# ESP-03_Breakout.net
KiCad netlist of a schematic drawn in EAGLE
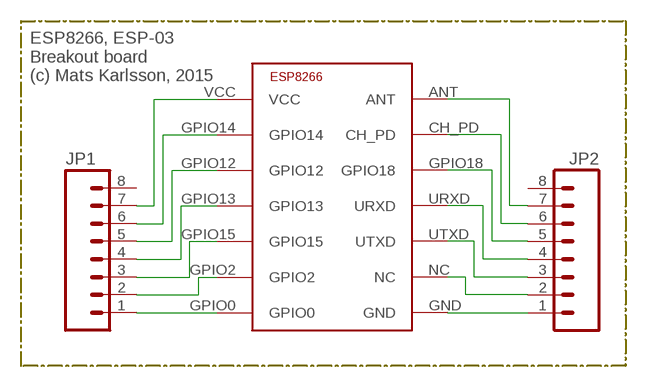
[diagram p0: schematic, sheet 1]

(export (version "E")
  (design (tool "Eeschema 10.0.6"))
  (components
    (comp (ref "JP1")
      (value "M08SMD-STRAIGHT-FEMALE")
      (footprint "eagle-import:1X08_SMD")
      (libsource (lib "eagle-import") (part "M08SMD-STRAIGHT-FEMALE"))
    )
    (comp (ref "JP2")
      (value "M08SMD-STRAIGHT-FEMALE")
      (footprint "eagle-import:1X08_SMD")
      (libsource (lib "eagle-import") (part "M08SMD-STRAIGHT-FEMALE"))
    )
    (comp (ref "U$1")
      (value "ESP8266-03")
      (footprint "eagle-import:ESP-03")
      (libsource (lib "eagle-import") (part "ESP8266-03"))
    )
  )
  (nets
    (net (code "1") (name "Net-(JP1-Pad1)") (class "Default")
      (node (ref "JP1") (pin "1") (pinfunction "1_1") (pintype "passive"))
      (node (ref "U$1") (pin "GPIO0") (pinfunction "GPIO0_GPIO0") (pintype "bidirectional"))
    )
    (net (code "2") (name "Net-(JP1-Pad2)") (class "Default")
      (node (ref "JP1") (pin "2") (pinfunction "2_2") (pintype "passive"))
      (node (ref "U$1") (pin "GPIO2") (pinfunction "GPIO2_GPIO2") (pintype "bidirectional"))
    )
    (net (code "3") (name "Net-(JP1-Pad3)") (class "Default")
      (node (ref "JP1") (pin "3") (pinfunction "3_3") (pintype "passive"))
      (node (ref "U$1") (pin "GPIO15") (pinfunction "GPIO15_GPIO15") (pintype "bidirectional"))
    )
    (net (code "4") (name "Net-(JP1-Pad4)") (class "Default")
      (node (ref "JP1") (pin "4") (pinfunction "4_4") (pintype "passive"))
      (node (ref "U$1") (pin "GPIO13") (pinfunction "GPIO13_GPIO13") (pintype "bidirectional"))
    )
    (net (code "5") (name "Net-(JP1-Pad5)") (class "Default")
      (node (ref "JP1") (pin "5") (pinfunction "5_5") (pintype "passive"))
      (node (ref "U$1") (pin "GPIO12") (pinfunction "GPIO12_GPIO12") (pintype "bidirectional"))
    )
    (net (code "6") (name "Net-(JP1-Pad6)") (class "Default")
      (node (ref "JP1") (pin "6") (pinfunction "6_6") (pintype "passive"))
      (node (ref "U$1") (pin "GPIO14") (pinfunction "GPIO14_GPIO14") (pintype "bidirectional"))
    )
    (net (code "7") (name "Net-(JP1-Pad7)") (class "Default")
      (node (ref "JP1") (pin "7") (pinfunction "7_7") (pintype "passive"))
      (node (ref "U$1") (pin "VCC") (pinfunction "VCC_VCC") (pintype "bidirectional"))
    )
    (net (code "8") (name "Net-(JP2-Pad1)") (class "Default")
      (node (ref "JP2") (pin "1") (pinfunction "1_1") (pintype "passive"))
      (node (ref "U$1") (pin "GND") (pinfunction "GND_GND") (pintype "bidirectional"))
    )
    (net (code "9") (name "Net-(JP2-Pad2)") (class "Default")
      (node (ref "JP2") (pin "2") (pinfunction "2_2") (pintype "passive"))
      (node (ref "U$1") (pin "NC") (pinfunction "NC_NC") (pintype "bidirectional"))
    )
    (net (code "10") (name "Net-(JP2-Pad3)") (class "Default")
      (node (ref "JP2") (pin "3") (pinfunction "3_3") (pintype "passive"))
      (node (ref "U$1") (pin "UTXD") (pinfunction "UTXD_UTXD") (pintype "bidirectional"))
    )
    (net (code "11") (name "Net-(JP2-Pad4)") (class "Default")
      (node (ref "JP2") (pin "4") (pinfunction "4_4") (pintype "passive"))
      (node (ref "U$1") (pin "URXD") (pinfunction "URXD_URXD") (pintype "bidirectional"))
    )
    (net (code "12") (name "Net-(JP2-Pad5)") (class "Default")
      (node (ref "JP2") (pin "5") (pinfunction "5_5") (pintype "passive"))
      (node (ref "U$1") (pin "GPIO18") (pinfunction "GPIO18_GPIO18") (pintype "bidirectional"))
    )
    (net (code "13") (name "Net-(JP2-Pad6)") (class "Default")
      (node (ref "JP2") (pin "6") (pinfunction "6_6") (pintype "passive"))
      (node (ref "U$1") (pin "CH_PD") (pinfunction "CH_PD_CH_PD") (pintype "bidirectional"))
    )
    (net (code "14") (name "Net-(JP2-Pad7)") (class "Default")
      (node (ref "JP2") (pin "7") (pinfunction "7_7") (pintype "passive"))
      (node (ref "U$1") (pin "ANT") (pinfunction "ANT_ANT") (pintype "bidirectional"))
    )
    (net (code "15") (name "unconnected-(JP1-Pad8)") (class "Default")
      (node (ref "JP1") (pin "8") (pinfunction "8_8") (pintype "passive"))
    )
    (net (code "16") (name "unconnected-(JP2-Pad8)") (class "Default")
      (node (ref "JP2") (pin "8") (pinfunction "8_8") (pintype "passive"))
    )
  )
)
